# Multi_Pitch_Sound_Generator_Project.net
KiCad netlist of a schematic drawn in Altium Designer
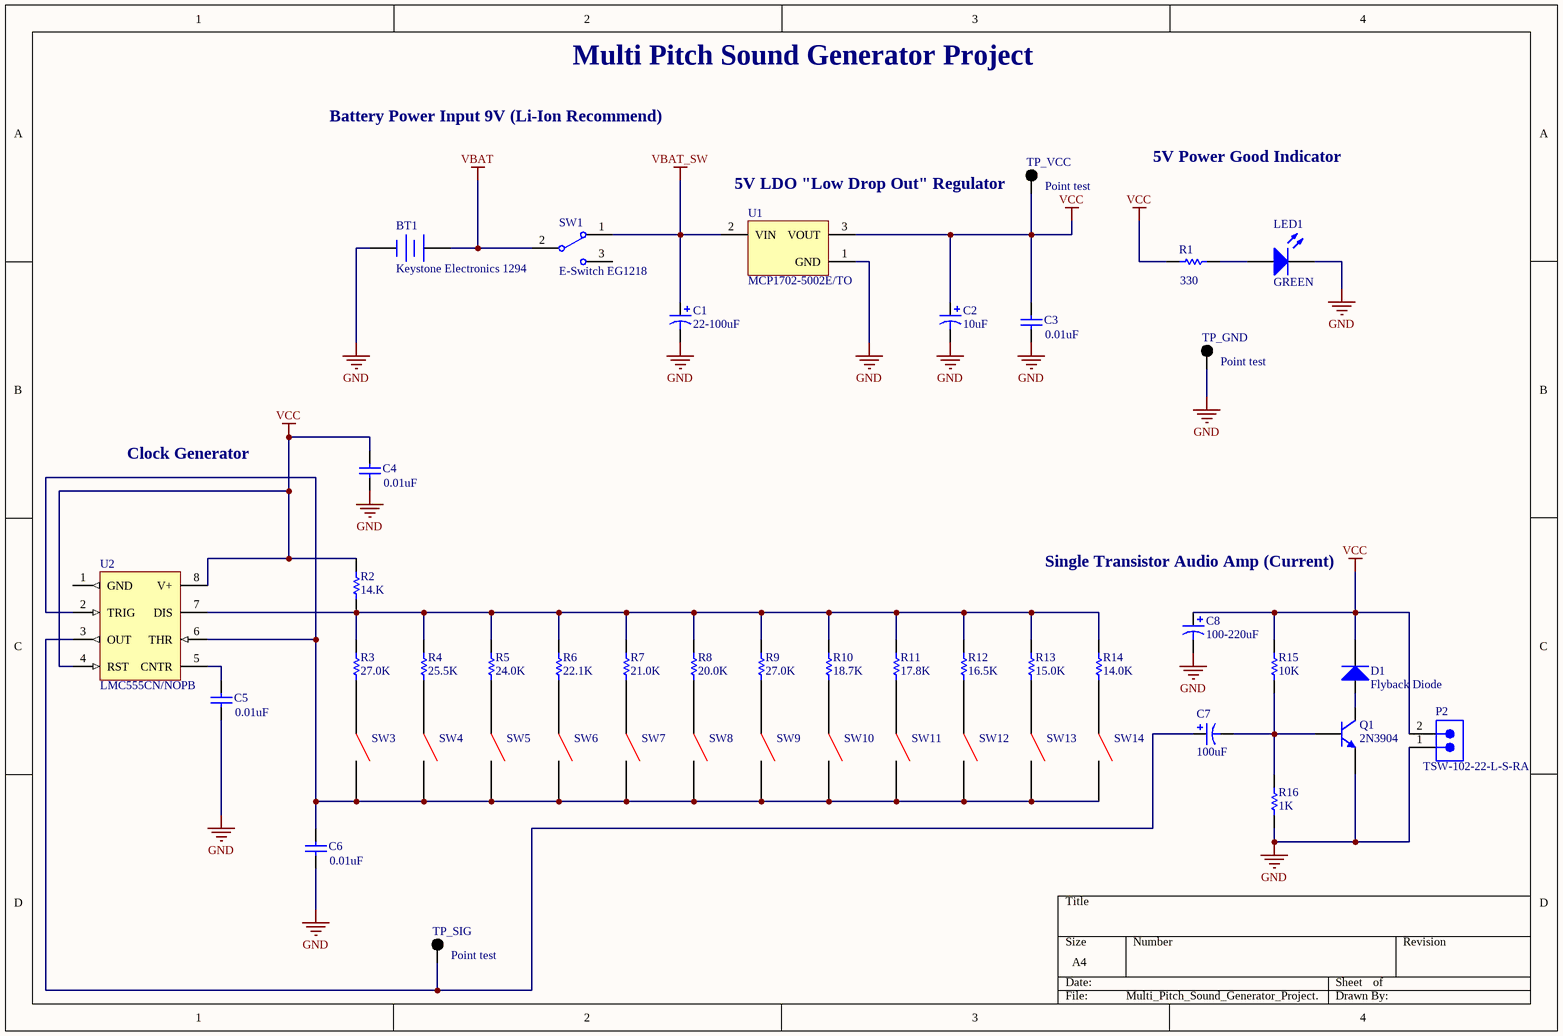
[diagram p0: Multi_Pitch_Sound_Generator_Project.SchDoc]

(export (version "E")
  (design (tool "Eeschema 10.0.6"))
  (components
    (comp (ref "BT1")
      (value "Keystone Electronics 1294")
      (footprint "PCB-3798-1")
      (description "HOLDER BATT 9V UNIV PLASTIC PC")
      (fields (field (name "MANUFACTURER PART NUMBER") "1294"))
      (libsource (lib "My Personal Space") (part "SYM-3798-1"))
    )
    (comp (ref "C1")
      (value "22-100uF")
      (footprint "PCB-nq6yd78wv7rl8ojp8omb-1")
      (description "Cap Aluminum 10uF 16V 20% (4 X 7mm) Cylindrical 18mA 7000 hr 105°C T/R")
      (fields (field (name "MANUFACTURER PART NUMBER") "UCB1C100MCL1GS"))
      (libsource (lib "My Personal Space") (part "SYM-119dd9bbe86bce5a-1"))
    )
    (comp (ref "C2")
      (value "10uF")
      (footprint "PCB-nq6yd78wv7rl8ojp8omb-1")
      (description "Cap Aluminum 10uF 16V 20% (4 X 7mm) Cylindrical 18mA 7000 hr 105°C T/R")
      (fields (field (name "MANUFACTURER PART NUMBER") "UCB1C100MCL1GS"))
      (libsource (lib "My Personal Space") (part "SYM-119dd9bbe86bce5a-1"))
    )
    (comp (ref "C3")
      (value "0.01uF")
      (footprint "PCB-ql28fbuo3tond8refhb5-1")
      (description "K 100nF Ceramic Multilayer Capacitor, 50 V dc, +125degC, X7R Dielectric, +/-10%")
      (libsource (lib "My Personal Space") (part "SYM-1272d9258f2acdb5-2"))
    )
    (comp (ref "C4")
      (value "0.01uF")
      (footprint "PCB-ql28fbuo3tond8refhb5-1")
      (description "K 100nF Ceramic Multilayer Capacitor, 50 V dc, +125degC, X7R Dielectric, +/-10%")
      (libsource (lib "My Personal Space") (part "SYM-1272d9258f2acdb5-2"))
    )
    (comp (ref "C5")
      (value "0.01uF")
      (footprint "PCB-ql28fbuo3tond8refhb5-1")
      (description "K 100nF Ceramic Multilayer Capacitor, 50 V dc, +125degC, X7R Dielectric, +/-10%")
      (libsource (lib "My Personal Space") (part "SYM-1272d9258f2acdb5-2"))
    )
    (comp (ref "C6")
      (value "0.01uF")
      (footprint "PCB-ql28fbuo3tond8refhb5-1")
      (description "K 100nF Ceramic Multilayer Capacitor, 50 V dc, +125degC, X7R Dielectric, +/-10%")
      (libsource (lib "My Personal Space") (part "SYM-1272d9258f2acdb5-2"))
    )
    (comp (ref "C7")
      (value "100uF")
      (footprint "PCB-nq6yd78wv7rl8ojp8omb-1")
      (description "Cap Aluminum 10uF 16V 20% (4 X 7mm) Cylindrical 18mA 7000 hr 105°C T/R")
      (fields (field (name "MANUFACTURER PART NUMBER") "UCB1C100MCL1GS"))
      (libsource (lib "My Personal Space") (part "SYM-119dd9bbe86bce5a-1"))
    )
    (comp (ref "C8")
      (value "100-220uF")
      (footprint "PCB-nq6yd78wv7rl8ojp8omb-1")
      (description "Cap Aluminum 10uF 16V 20% (4 X 7mm) Cylindrical 18mA 7000 hr 105°C T/R")
      (fields (field (name "MANUFACTURER PART NUMBER") "UCB1C100MCL1GS"))
      (libsource (lib "My Personal Space") (part "SYM-119dd9bbe86bce5a-1"))
    )
    (comp (ref "D1")
      (value "Flyback Diode")
      (footprint "PCB-z2ypi7zr74mzpyjelpsh-1")
      (description "Standard Recovery Rectifier, 2-Pin Axial_Lead, Pb-Free, Tape and Reel")
      (fields (field (name "MANUFACTURER PART NUMBER") "1N4001RLG"))
      (libsource (lib "My Personal Space") (part "SYM-e02d2927e6e83fea-1"))
    )
    (comp (ref "LED1")
      (value "GREEN")
      (footprint "PCB-b5vk7vz0xhkw7l0fnova-1")
      (description "LED Uni-Color Green 2-Pin T-1 3/4 Bulk")
      (fields
        (field (name "MANUFACTURER PART NUMBER") "C503B-GCN-CY0C0791")
        (field (name "MANUFACTURER") "Cree")
      )
      (libsource (lib "My Personal Space") (part "SYM-92bb5b2eff764d7c-1"))
    )
    (comp (ref "P2")
      (value "TSW-102-22-L-S-RA")
      (footprint "SMTC-TSW-102-22-X-S-RA")
      (libsource (lib "My Personal Space") (part "SMTC-TSW-102-X-X-S-X"))
    )
    (comp (ref "Q1")
      (value "2N3904")
      (footprint "PCB-d52vzgbszc9onplxz1b0-1")
      (description "Transistor General Purpose BJT NPN 40 Volt 0.2 Amp 3-Pin TO-92 Tape And Reel")
      (fields (field (name "MANUFACTURER PART NUMBER") "2N3904TF"))
      (libsource (lib "My Personal Space") (part "2N3904"))
    )
    (comp (ref "R1")
      (value "330")
      (footprint "PCB-0jk5y5qyb1smy9vf6b7t-1")
      (description "Res, 1K, 250mW, 5%, Axial")
      (libsource (lib "My Personal Space") (part "SYM-db3e1311f37e04f9-4"))
    )
    (comp (ref "R2")
      (value "14.K")
      (footprint "PCB-0jk5y5qyb1smy9vf6b7t-1")
      (description "Res, 1K, 250mW, 5%, Axial")
      (libsource (lib "My Personal Space") (part "SYM-db3e1311f37e04f9-4"))
    )
    (comp (ref "R3")
      (value "27.0K")
      (footprint "PCB-0jk5y5qyb1smy9vf6b7t-1")
      (description "Res, 1K, 250mW, 5%, Axial")
      (libsource (lib "My Personal Space") (part "SYM-db3e1311f37e04f9-4"))
    )
    (comp (ref "R4")
      (value "25.5K")
      (footprint "PCB-0jk5y5qyb1smy9vf6b7t-1")
      (description "Res, 1K, 250mW, 5%, Axial")
      (libsource (lib "My Personal Space") (part "SYM-db3e1311f37e04f9-4"))
    )
    (comp (ref "R5")
      (value "24.0K")
      (footprint "PCB-0jk5y5qyb1smy9vf6b7t-1")
      (description "Res, 1K, 250mW, 5%, Axial")
      (libsource (lib "My Personal Space") (part "SYM-db3e1311f37e04f9-4"))
    )
    (comp (ref "R6")
      (value "22.1K")
      (footprint "PCB-0jk5y5qyb1smy9vf6b7t-1")
      (description "Res, 1K, 250mW, 5%, Axial")
      (libsource (lib "My Personal Space") (part "SYM-db3e1311f37e04f9-4"))
    )
    (comp (ref "R7")
      (value "21.0K")
      (footprint "PCB-0jk5y5qyb1smy9vf6b7t-1")
      (description "Res, 1K, 250mW, 5%, Axial")
      (libsource (lib "My Personal Space") (part "SYM-db3e1311f37e04f9-4"))
    )
    (comp (ref "R8")
      (value "20.0K")
      (footprint "PCB-0jk5y5qyb1smy9vf6b7t-1")
      (description "Res, 1K, 250mW, 5%, Axial")
      (libsource (lib "My Personal Space") (part "SYM-db3e1311f37e04f9-4"))
    )
    (comp (ref "R9")
      (value "27.0K")
      (footprint "PCB-0jk5y5qyb1smy9vf6b7t-1")
      (description "Res, 1K, 250mW, 5%, Axial")
      (libsource (lib "My Personal Space") (part "SYM-db3e1311f37e04f9-4"))
    )
    (comp (ref "R10")
      (value "18.7K")
      (footprint "PCB-0jk5y5qyb1smy9vf6b7t-1")
      (description "Res, 1K, 250mW, 5%, Axial")
      (libsource (lib "My Personal Space") (part "SYM-db3e1311f37e04f9-4"))
    )
    (comp (ref "R11")
      (value "17.8K")
      (footprint "PCB-0jk5y5qyb1smy9vf6b7t-1")
      (description "Res, 1K, 250mW, 5%, Axial")
      (libsource (lib "My Personal Space") (part "SYM-db3e1311f37e04f9-4"))
    )
    (comp (ref "R12")
      (value "16.5K")
      (footprint "PCB-0jk5y5qyb1smy9vf6b7t-1")
      (description "Res, 1K, 250mW, 5%, Axial")
      (libsource (lib "My Personal Space") (part "SYM-db3e1311f37e04f9-4"))
    )
    (comp (ref "R13")
      (value "15.0K")
      (footprint "PCB-0jk5y5qyb1smy9vf6b7t-1")
      (description "Res, 1K, 250mW, 5%, Axial")
      (libsource (lib "My Personal Space") (part "SYM-db3e1311f37e04f9-4"))
    )
    (comp (ref "R14")
      (value "14.0K")
      (footprint "PCB-0jk5y5qyb1smy9vf6b7t-1")
      (description "Res, 1K, 250mW, 5%, Axial")
      (libsource (lib "My Personal Space") (part "SYM-db3e1311f37e04f9-4"))
    )
    (comp (ref "R15")
      (value "10K")
      (footprint "PCB-0jk5y5qyb1smy9vf6b7t-1")
      (description "Res, 1K, 250mW, 5%, Axial")
      (libsource (lib "My Personal Space") (part "SYM-db3e1311f37e04f9-4"))
    )
    (comp (ref "R16")
      (value "1K")
      (footprint "PCB-0jk5y5qyb1smy9vf6b7t-1")
      (description "Res, 1K, 250mW, 5%, Axial")
      (libsource (lib "My Personal Space") (part "SYM-db3e1311f37e04f9-4"))
    )
    (comp (ref "SW1")
      (value "E-Switch EG1218")
      (footprint "ESWI-EG1218_V")
      (description "Slide Switch, 500 V, -20 to 70 degC, 3-Pin THD, RoHS")
      (fields (field (name "MANUFACTURER PART NUMBER") "EG1218"))
      (libsource (lib "My Personal Space") (part "SW-SPDT-3_B"))
    )
    (comp (ref "SW3")
      (value "~")
      (footprint "PCB-je10m8m3eogq13l465bo-1")
      (description "Switch Tactile N.O. SPST Round Button PC Pins 0.02A 15VDC 1.3N Thru-Hole Radial T/R")
      (fields
        (field (name "ELEMENT14 PART NO.") "2281982")
        (field (name "MANUFACTURER PART NUMBER") "EVQ-21405R")
      )
      (libsource (lib "My Personal Space") (part "SYM-2fe5e5be239cf022-1"))
    )
    (comp (ref "SW4")
      (value "~")
      (footprint "PCB-je10m8m3eogq13l465bo-1")
      (description "Switch Tactile N.O. SPST Round Button PC Pins 0.02A 15VDC 1.3N Thru-Hole Radial T/R")
      (fields
        (field (name "ELEMENT14 PART NO.") "2281982")
        (field (name "MANUFACTURER PART NUMBER") "EVQ-21405R")
      )
      (libsource (lib "My Personal Space") (part "SYM-2fe5e5be239cf022-1"))
    )
    (comp (ref "SW5")
      (value "~")
      (footprint "PCB-je10m8m3eogq13l465bo-1")
      (description "Switch Tactile N.O. SPST Round Button PC Pins 0.02A 15VDC 1.3N Thru-Hole Radial T/R")
      (fields
        (field (name "ELEMENT14 PART NO.") "2281982")
        (field (name "MANUFACTURER PART NUMBER") "EVQ-21405R")
      )
      (libsource (lib "My Personal Space") (part "SYM-2fe5e5be239cf022-1"))
    )
    (comp (ref "SW6")
      (value "~")
      (footprint "PCB-je10m8m3eogq13l465bo-1")
      (description "Switch Tactile N.O. SPST Round Button PC Pins 0.02A 15VDC 1.3N Thru-Hole Radial T/R")
      (fields
        (field (name "ELEMENT14 PART NO.") "2281982")
        (field (name "MANUFACTURER PART NUMBER") "EVQ-21405R")
      )
      (libsource (lib "My Personal Space") (part "SYM-2fe5e5be239cf022-1"))
    )
    (comp (ref "SW7")
      (value "~")
      (footprint "PCB-je10m8m3eogq13l465bo-1")
      (description "Switch Tactile N.O. SPST Round Button PC Pins 0.02A 15VDC 1.3N Thru-Hole Radial T/R")
      (fields
        (field (name "ELEMENT14 PART NO.") "2281982")
        (field (name "MANUFACTURER PART NUMBER") "EVQ-21405R")
      )
      (libsource (lib "My Personal Space") (part "SYM-2fe5e5be239cf022-1"))
    )
    (comp (ref "SW8")
      (value "~")
      (footprint "PCB-je10m8m3eogq13l465bo-1")
      (description "Switch Tactile N.O. SPST Round Button PC Pins 0.02A 15VDC 1.3N Thru-Hole Radial T/R")
      (fields
        (field (name "ELEMENT14 PART NO.") "2281982")
        (field (name "MANUFACTURER PART NUMBER") "EVQ-21405R")
      )
      (libsource (lib "My Personal Space") (part "SYM-2fe5e5be239cf022-1"))
    )
    (comp (ref "SW9")
      (value "~")
      (footprint "PCB-je10m8m3eogq13l465bo-1")
      (description "Switch Tactile N.O. SPST Round Button PC Pins 0.02A 15VDC 1.3N Thru-Hole Radial T/R")
      (fields
        (field (name "ELEMENT14 PART NO.") "2281982")
        (field (name "MANUFACTURER PART NUMBER") "EVQ-21405R")
      )
      (libsource (lib "My Personal Space") (part "SYM-2fe5e5be239cf022-1"))
    )
    (comp (ref "SW10")
      (value "~")
      (footprint "PCB-je10m8m3eogq13l465bo-1")
      (description "Switch Tactile N.O. SPST Round Button PC Pins 0.02A 15VDC 1.3N Thru-Hole Radial T/R")
      (fields
        (field (name "ELEMENT14 PART NO.") "2281982")
        (field (name "MANUFACTURER PART NUMBER") "EVQ-21405R")
      )
      (libsource (lib "My Personal Space") (part "SYM-2fe5e5be239cf022-1"))
    )
    (comp (ref "SW11")
      (value "~")
      (footprint "PCB-je10m8m3eogq13l465bo-1")
      (description "Switch Tactile N.O. SPST Round Button PC Pins 0.02A 15VDC 1.3N Thru-Hole Radial T/R")
      (fields
        (field (name "ELEMENT14 PART NO.") "2281982")
        (field (name "MANUFACTURER PART NUMBER") "EVQ-21405R")
      )
      (libsource (lib "My Personal Space") (part "SYM-2fe5e5be239cf022-1"))
    )
    (comp (ref "SW12")
      (value "~")
      (footprint "PCB-je10m8m3eogq13l465bo-1")
      (description "Switch Tactile N.O. SPST Round Button PC Pins 0.02A 15VDC 1.3N Thru-Hole Radial T/R")
      (fields
        (field (name "ELEMENT14 PART NO.") "2281982")
        (field (name "MANUFACTURER PART NUMBER") "EVQ-21405R")
      )
      (libsource (lib "My Personal Space") (part "SYM-2fe5e5be239cf022-1"))
    )
    (comp (ref "SW13")
      (value "~")
      (footprint "PCB-je10m8m3eogq13l465bo-1")
      (description "Switch Tactile N.O. SPST Round Button PC Pins 0.02A 15VDC 1.3N Thru-Hole Radial T/R")
      (fields
        (field (name "ELEMENT14 PART NO.") "2281982")
        (field (name "MANUFACTURER PART NUMBER") "EVQ-21405R")
      )
      (libsource (lib "My Personal Space") (part "SYM-2fe5e5be239cf022-1"))
    )
    (comp (ref "SW14")
      (value "~")
      (footprint "PCB-je10m8m3eogq13l465bo-1")
      (description "Switch Tactile N.O. SPST Round Button PC Pins 0.02A 15VDC 1.3N Thru-Hole Radial T/R")
      (fields
        (field (name "ELEMENT14 PART NO.") "2281982")
        (field (name "MANUFACTURER PART NUMBER") "EVQ-21405R")
      )
      (libsource (lib "My Personal Space") (part "SYM-2fe5e5be239cf022-1"))
    )
    (comp (ref "TP_GND")
      (value "Point test")
      (footprint "P1-09")
      (description "KEYSTONE   5001   TEST POINT, PCB, THROUGH HOLE")
      (libsource (lib "My Personal Space") (part "KSTN-5001"))
    )
    (comp (ref "TP_SIG")
      (value "Point test")
      (footprint "P1-09")
      (description "KEYSTONE   5001   TEST POINT, PCB, THROUGH HOLE")
      (libsource (lib "My Personal Space") (part "KSTN-5001"))
    )
    (comp (ref "TP_VCC")
      (value "Point test")
      (footprint "P1-09")
      (description "KEYSTONE   5001   TEST POINT, PCB, THROUGH HOLE")
      (libsource (lib "My Personal Space") (part "KSTN-5001"))
    )
    (comp (ref "U1")
      (value "MCP1702-5002E/TO")
      (footprint "TO-92-TO3")
      (description "250 mA Low Quiescent Current LDO Regulator, 3-Pin TO-92, Extended TemperatureBAG")
      (libsource (lib "My Personal Space") (part "PM-LINEREG-MCP1702-IL3A"))
    )
    (comp (ref "U2")
      (value "LMC555CN/NOPB")
      (footprint "TI-D8_L")
      (description "World’s smallest 555 timer with low power, high accuracy and a Fmax of 3MHz 8-SOIC -40 to 85")
      (fields (field (name "MANUFACTURER PART NUMBER") "LMC555CMX/NOPB"))
      (libsource (lib "My Personal Space") (part "INF-TLE5012BE5000-PG-DSO-8-16-8"))
    )
  )
  (nets
    (net (code "1") (name "GND") (class "Default")
      (node (ref "BT1") (pin "2") (pinfunction "-_2") (pintype "passive"))
      (node (ref "C1") (pin "2") (pinfunction "2_2") (pintype "passive"))
      (node (ref "C2") (pin "2") (pinfunction "2_2") (pintype "passive"))
      (node (ref "C3") (pin "1") (pinfunction "1_1") (pintype "passive"))
      (node (ref "C4") (pin "1") (pinfunction "1_1") (pintype "passive"))
      (node (ref "C5") (pin "1") (pinfunction "1_1") (pintype "passive"))
      (node (ref "C6") (pin "1") (pinfunction "1_1") (pintype "passive"))
      (node (ref "C8") (pin "2") (pinfunction "2_2") (pintype "passive"))
      (node (ref "LED1") (pin "1") (pinfunction "K_1") (pintype "passive"))
      (node (ref "P2") (pin "1") (pinfunction "1_1") (pintype "passive"))
      (node (ref "Q1") (pin "E") (pinfunction "E_E") (pintype "passive"))
      (node (ref "R16") (pin "2") (pinfunction "2_2") (pintype "passive"))
      (node (ref "TP_GND") (pin "1") (pinfunction "1_1") (pintype "passive"))
      (node (ref "U1") (pin "1") (pinfunction "GND_1") (pintype "power_in"))
    )
    (net (code "2") (name "Net-(C7-Pad2)") (class "Default")
      (node (ref "C7") (pin "2") (pinfunction "2_2") (pintype "passive"))
      (node (ref "Q1") (pin "B") (pinfunction "B_B") (pintype "passive"))
      (node (ref "R15") (pin "2") (pinfunction "2_2") (pintype "passive"))
      (node (ref "R16") (pin "1") (pinfunction "1_1") (pintype "passive"))
    )
    (net (code "3") (name "Net-(D1-A)") (class "Default")
      (node (ref "D1") (pin "1") (pinfunction "A_1") (pintype "passive"))
      (node (ref "Q1") (pin "C") (pinfunction "C_C") (pintype "passive"))
    )
    (net (code "4") (name "Net-(LED1-A)") (class "Default")
      (node (ref "LED1") (pin "2") (pinfunction "A_2") (pintype "passive"))
      (node (ref "R1") (pin "2") (pinfunction "2_2") (pintype "passive"))
    )
    (net (code "5") (name "Net-(R3-Pad2)") (class "Default")
      (node (ref "R3") (pin "2") (pinfunction "2_2") (pintype "passive"))
      (node (ref "SW3") (pin "1") (pinfunction "1_1") (pintype "passive"))
    )
    (net (code "6") (name "Net-(R4-Pad2)") (class "Default")
      (node (ref "R4") (pin "2") (pinfunction "2_2") (pintype "passive"))
      (node (ref "SW4") (pin "1") (pinfunction "1_1") (pintype "passive"))
    )
    (net (code "7") (name "Net-(R5-Pad2)") (class "Default")
      (node (ref "R5") (pin "2") (pinfunction "2_2") (pintype "passive"))
      (node (ref "SW5") (pin "1") (pinfunction "1_1") (pintype "passive"))
    )
    (net (code "8") (name "Net-(R6-Pad2)") (class "Default")
      (node (ref "R6") (pin "2") (pinfunction "2_2") (pintype "passive"))
      (node (ref "SW6") (pin "1") (pinfunction "1_1") (pintype "passive"))
    )
    (net (code "9") (name "Net-(R7-Pad2)") (class "Default")
      (node (ref "R7") (pin "2") (pinfunction "2_2") (pintype "passive"))
      (node (ref "SW7") (pin "1") (pinfunction "1_1") (pintype "passive"))
    )
    (net (code "10") (name "Net-(R8-Pad2)") (class "Default")
      (node (ref "R8") (pin "2") (pinfunction "2_2") (pintype "passive"))
      (node (ref "SW8") (pin "1") (pinfunction "1_1") (pintype "passive"))
    )
    (net (code "11") (name "Net-(R9-Pad2)") (class "Default")
      (node (ref "R9") (pin "2") (pinfunction "2_2") (pintype "passive"))
      (node (ref "SW9") (pin "1") (pinfunction "1_1") (pintype "passive"))
    )
    (net (code "12") (name "Net-(R10-Pad2)") (class "Default")
      (node (ref "R10") (pin "2") (pinfunction "2_2") (pintype "passive"))
      (node (ref "SW10") (pin "1") (pinfunction "1_1") (pintype "passive"))
    )
    (net (code "13") (name "Net-(R11-Pad2)") (class "Default")
      (node (ref "R11") (pin "2") (pinfunction "2_2") (pintype "passive"))
      (node (ref "SW11") (pin "1") (pinfunction "1_1") (pintype "passive"))
    )
    (net (code "14") (name "Net-(R12-Pad2)") (class "Default")
      (node (ref "R12") (pin "2") (pinfunction "2_2") (pintype "passive"))
      (node (ref "SW12") (pin "1") (pinfunction "1_1") (pintype "passive"))
    )
    (net (code "15") (name "Net-(R13-Pad2)") (class "Default")
      (node (ref "R13") (pin "2") (pinfunction "2_2") (pintype "passive"))
      (node (ref "SW13") (pin "1") (pinfunction "1_1") (pintype "passive"))
    )
    (net (code "16") (name "Net-(R14-Pad2)") (class "Default")
      (node (ref "R14") (pin "2") (pinfunction "2_2") (pintype "passive"))
      (node (ref "SW14") (pin "1") (pinfunction "1_1") (pintype "passive"))
    )
    (net (code "17") (name "Net-(U2-CNTR)") (class "Default")
      (node (ref "C5") (pin "2") (pinfunction "2_2") (pintype "passive"))
      (node (ref "U2") (pin "5") (pinfunction "CNTR_5") (pintype "passive"))
    )
    (net (code "18") (name "Net-(U2-DIS)") (class "Default")
      (node (ref "R10") (pin "1") (pinfunction "1_1") (pintype "passive"))
      (node (ref "R11") (pin "1") (pinfunction "1_1") (pintype "passive"))
      (node (ref "R12") (pin "1") (pinfunction "1_1") (pintype "passive"))
      (node (ref "R13") (pin "1") (pinfunction "1_1") (pintype "passive"))
      (node (ref "R14") (pin "1") (pinfunction "1_1") (pintype "passive"))
      (node (ref "R2") (pin "2") (pinfunction "2_2") (pintype "passive"))
      (node (ref "R3") (pin "1") (pinfunction "1_1") (pintype "passive"))
      (node (ref "R4") (pin "1") (pinfunction "1_1") (pintype "passive"))
      (node (ref "R5") (pin "1") (pinfunction "1_1") (pintype "passive"))
      (node (ref "R6") (pin "1") (pinfunction "1_1") (pintype "passive"))
      (node (ref "R7") (pin "1") (pinfunction "1_1") (pintype "passive"))
      (node (ref "R8") (pin "1") (pinfunction "1_1") (pintype "passive"))
      (node (ref "R9") (pin "1") (pinfunction "1_1") (pintype "passive"))
      (node (ref "U2") (pin "7") (pinfunction "DIS_7") (pintype "passive"))
    )
    (net (code "19") (name "Net-(U2-OUT)") (class "Default")
      (node (ref "C7") (pin "1") (pinfunction "1_1") (pintype "passive"))
      (node (ref "TP_SIG") (pin "1") (pinfunction "1_1") (pintype "passive"))
      (node (ref "U2") (pin "3") (pinfunction "OUT_3") (pintype "output"))
    )
    (net (code "20") (name "Net-(U2-THR)") (class "Default")
      (node (ref "C6") (pin "2") (pinfunction "2_2") (pintype "passive"))
      (node (ref "SW10") (pin "2") (pinfunction "2_2") (pintype "passive"))
      (node (ref "SW11") (pin "2") (pinfunction "2_2") (pintype "passive"))
      (node (ref "SW12") (pin "2") (pinfunction "2_2") (pintype "passive"))
      (node (ref "SW13") (pin "2") (pinfunction "2_2") (pintype "passive"))
      (node (ref "SW14") (pin "2") (pinfunction "2_2") (pintype "passive"))
      (node (ref "SW3") (pin "2") (pinfunction "2_2") (pintype "passive"))
      (node (ref "SW4") (pin "2") (pinfunction "2_2") (pintype "passive"))
      (node (ref "SW5") (pin "2") (pinfunction "2_2") (pintype "passive"))
      (node (ref "SW6") (pin "2") (pinfunction "2_2") (pintype "passive"))
      (node (ref "SW7") (pin "2") (pinfunction "2_2") (pintype "passive"))
      (node (ref "SW8") (pin "2") (pinfunction "2_2") (pintype "passive"))
      (node (ref "SW9") (pin "2") (pinfunction "2_2") (pintype "passive"))
      (node (ref "U2") (pin "2") (pinfunction "TRIG_2") (pintype "input"))
      (node (ref "U2") (pin "6") (pinfunction "THR_6") (pintype "input"))
    )
    (net (code "21") (name "VBAT") (class "Default")
      (node (ref "BT1") (pin "1") (pinfunction "+_1") (pintype "passive"))
      (node (ref "SW1") (pin "2") (pinfunction "COM_2") (pintype "passive"))
    )
    (net (code "22") (name "VBAT_SW") (class "Default")
      (node (ref "C1") (pin "1") (pinfunction "1_1") (pintype "passive"))
      (node (ref "SW1") (pin "1") (pinfunction "1_1") (pintype "passive"))
      (node (ref "U1") (pin "2") (pinfunction "VIN_2") (pintype "power_in"))
    )
    (net (code "23") (name "VCC") (class "Default")
      (node (ref "C2") (pin "1") (pinfunction "1_1") (pintype "passive"))
      (node (ref "C3") (pin "2") (pinfunction "2_2") (pintype "passive"))
      (node (ref "C4") (pin "2") (pinfunction "2_2") (pintype "passive"))
      (node (ref "C8") (pin "1") (pinfunction "1_1") (pintype "passive"))
      (node (ref "D1") (pin "2") (pinfunction "K_2") (pintype "passive"))
      (node (ref "P2") (pin "2") (pinfunction "2_2") (pintype "passive"))
      (node (ref "R1") (pin "1") (pinfunction "1_1") (pintype "passive"))
      (node (ref "R15") (pin "1") (pinfunction "1_1") (pintype "passive"))
      (node (ref "R2") (pin "1") (pinfunction "1_1") (pintype "passive"))
      (node (ref "TP_VCC") (pin "1") (pinfunction "1_1") (pintype "passive"))
      (node (ref "U1") (pin "3") (pinfunction "VOUT_3") (pintype "power_in"))
      (node (ref "U2") (pin "4") (pinfunction "RST_4") (pintype "input"))
      (node (ref "U2") (pin "8") (pinfunction "V+_8") (pintype "power_in"))
    )
    (net (code "24") (name "unconnected-(SW1-Pad3)") (class "Default")
      (node (ref "SW1") (pin "3") (pinfunction "3_3") (pintype "passive"))
    )
    (net (code "25") (name "unconnected-(U2-GND-Pad1)") (class "Default")
      (node (ref "U2") (pin "1") (pinfunction "GND_1") (pintype "output"))
    )
  )
)
